# max3232.net
KiCad netlist of a schematic drawn in EAGLE
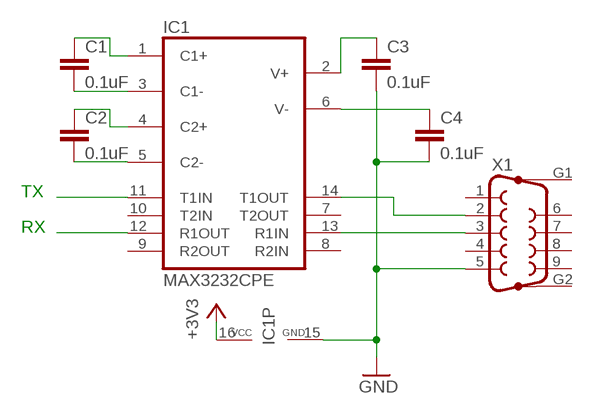
[diagram p0: schematic, sheet 1]

(export (version "E")
  (design (tool "Eeschema 10.0.6"))
  (components
    (comp (ref "C1")
      (value "0.1uF")
      (footprint "eagle-import:C025-024X044")
      (libsource (lib "eagle-import") (part "C-EU025-024X044"))
    )
    (comp (ref "C2")
      (value "0.1uF")
      (footprint "eagle-import:C025-024X044")
      (libsource (lib "eagle-import") (part "C-EU025-024X044"))
    )
    (comp (ref "C3")
      (value "0.1uF")
      (footprint "eagle-import:C025-024X044")
      (libsource (lib "eagle-import") (part "C-EU025-024X044"))
    )
    (comp (ref "C4")
      (value "0.1uF")
      (footprint "eagle-import:C025-024X044")
      (libsource (lib "eagle-import") (part "C-EU025-024X044"))
    )
    (comp (ref "IC1")
      (value "MAX3232CPE")
      (footprint "eagle-import:DIL16")
      (fields (field (name "MF") "MAXIM") (field (name "MPN") "MAX3232CPE+"))
      (libsource (lib "eagle-import") (part "MAX3232PEC"))
    )
    (comp (ref "X1")
      (value "F09HP")
      (footprint "eagle-import:F09HP")
      (libsource (lib "eagle-import") (part "F09HP"))
    )
  )
  (nets
    (net (code "1") (name "+3V3") (class "Default")
      (node (ref "IC1") (pin "16") (pinfunction "VCC_16") (pintype "power_in"))
    )
    (net (code "2") (name "GND") (class "Default")
      (node (ref "C3") (pin "2") (pinfunction "2_2") (pintype "passive"))
      (node (ref "C4") (pin "2") (pinfunction "2_2") (pintype "passive"))
      (node (ref "IC1") (pin "15") (pinfunction "GND_15") (pintype "power_in"))
      (node (ref "X1") (pin "5") (pinfunction "5_5") (pintype "passive"))
    )
    (net (code "3") (name "Net-(IC1A-C1+)") (class "Default")
      (node (ref "C1") (pin "1") (pinfunction "1_1") (pintype "passive"))
      (node (ref "IC1") (pin "1") (pinfunction "C1+_1") (pintype "bidirectional"))
    )
    (net (code "4") (name "Net-(IC1A-C1-)") (class "Default")
      (node (ref "C1") (pin "2") (pinfunction "2_2") (pintype "passive"))
      (node (ref "IC1") (pin "3") (pinfunction "C1-_3") (pintype "bidirectional"))
    )
    (net (code "5") (name "Net-(IC1A-C2+)") (class "Default")
      (node (ref "C2") (pin "1") (pinfunction "1_1") (pintype "passive"))
      (node (ref "IC1") (pin "4") (pinfunction "C2+_4") (pintype "bidirectional"))
    )
    (net (code "6") (name "Net-(IC1A-C2-)") (class "Default")
      (node (ref "C2") (pin "2") (pinfunction "2_2") (pintype "passive"))
      (node (ref "IC1") (pin "5") (pinfunction "C2-_5") (pintype "bidirectional"))
    )
    (net (code "7") (name "Net-(IC1A-R1IN)") (class "Default")
      (node (ref "IC1") (pin "13") (pinfunction "R1IN_13") (pintype "input"))
      (node (ref "X1") (pin "3") (pinfunction "3_3") (pintype "passive"))
    )
    (net (code "8") (name "Net-(IC1A-T1OUT)") (class "Default")
      (node (ref "IC1") (pin "14") (pinfunction "T1OUT_14") (pintype "output"))
      (node (ref "X1") (pin "2") (pinfunction "2_2") (pintype "passive"))
    )
    (net (code "9") (name "Net-(IC1A-V+)") (class "Default")
      (node (ref "C3") (pin "1") (pinfunction "1_1") (pintype "passive"))
      (node (ref "IC1") (pin "2") (pinfunction "V+_2") (pintype "bidirectional"))
    )
    (net (code "10") (name "Net-(IC1A-V-)") (class "Default")
      (node (ref "C4") (pin "1") (pinfunction "1_1") (pintype "passive"))
      (node (ref "IC1") (pin "6") (pinfunction "V-_6") (pintype "bidirectional"))
    )
    (net (code "11") (name "unconnected-(IC1A-R1OUT-Pad12)") (class "Default")
      (node (ref "IC1") (pin "12") (pinfunction "R1OUT_12") (pintype "output"))
    )
    (net (code "12") (name "unconnected-(IC1A-R2IN-Pad8)") (class "Default")
      (node (ref "IC1") (pin "8") (pinfunction "R2IN_8") (pintype "input"))
    )
    (net (code "13") (name "unconnected-(IC1A-R2OUT-Pad9)") (class "Default")
      (node (ref "IC1") (pin "9") (pinfunction "R2OUT_9") (pintype "output"))
    )
    (net (code "14") (name "unconnected-(IC1A-T1IN-Pad11)") (class "Default")
      (node (ref "IC1") (pin "11") (pinfunction "T1IN_11") (pintype "input"))
    )
    (net (code "15") (name "unconnected-(IC1A-T2IN-Pad10)") (class "Default")
      (node (ref "IC1") (pin "10") (pinfunction "T2IN_10") (pintype "input"))
    )
    (net (code "16") (name "unconnected-(IC1A-T2OUT-Pad7)") (class "Default")
      (node (ref "IC1") (pin "7") (pinfunction "T2OUT_7") (pintype "output"))
    )
    (net (code "17") (name "unconnected-(X1-Pad1)") (class "Default")
      (node (ref "X1") (pin "1") (pinfunction "1_1") (pintype "passive"))
    )
    (net (code "18") (name "unconnected-(X1-Pad4)") (class "Default")
      (node (ref "X1") (pin "4") (pinfunction "4_4") (pintype "passive"))
    )
    (net (code "19") (name "unconnected-(X1-Pad6)") (class "Default")
      (node (ref "X1") (pin "6") (pinfunction "6_6") (pintype "passive"))
    )
    (net (code "20") (name "unconnected-(X1-Pad7)") (class "Default")
      (node (ref "X1") (pin "7") (pinfunction "7_7") (pintype "passive"))
    )
    (net (code "21") (name "unconnected-(X1-Pad8)") (class "Default")
      (node (ref "X1") (pin "8") (pinfunction "8_8") (pintype "passive"))
    )
    (net (code "22") (name "unconnected-(X1-Pad9)") (class "Default")
      (node (ref "X1") (pin "9") (pinfunction "9_9") (pintype "passive"))
    )
    (net (code "23") (name "unconnected-(X1-PadG1)") (class "Default")
      (node (ref "X1") (pin "G1") (pinfunction "G1_G1") (pintype "passive"))
    )
    (net (code "24") (name "unconnected-(X1-PadG2)") (class "Default")
      (node (ref "X1") (pin "G2") (pinfunction "G2_G2") (pintype "passive"))
    )
  )
)
